# psu_toggle_switch.net
KiCad netlist of a schematic drawn in Altium Designer
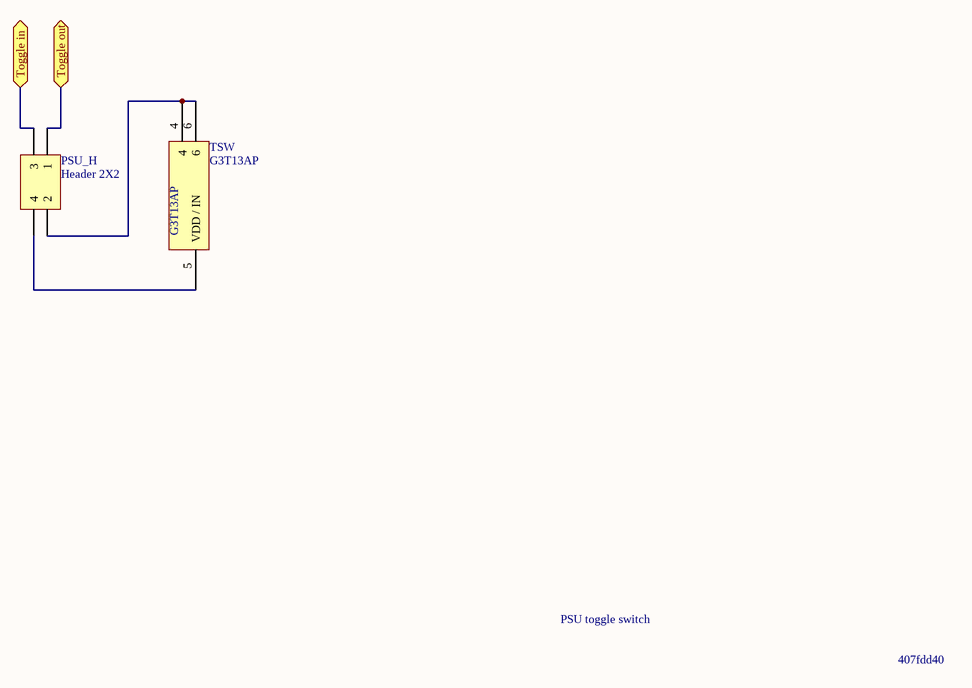
[diagram p0: psu_toggle_switch.SchDoc]

(export (version "E")
  (design (tool "Eeschema 10.0.6"))
  (components
    (comp (ref "PSU_H")
      (value "Header 2X2")
      (footprint "HDR2X2")
      (description "Header, 2-Pin, Dual row")
      (fields (field (name "PUBLISHER") "Altium Limited"))
      (libsource (lib "Miscellaneous Connectors") (part "Header 2X2"))
    )
    (comp (ref "TSW")
      (value "G3T13AP")
      (footprint "G3T13AP")
      (libsource (lib "switch-toggle") (part "G3T13AP"))
    )
  )
  (nets
    (net (code "1") (name "/Toggle in") (class "Default")
      (node (ref "PSU_H") (pin "3") (pinfunction "3_3") (pintype "passive"))
    )
    (net (code "2") (name "/Toggle out") (class "Default")
      (node (ref "PSU_H") (pin "1") (pinfunction "1_1") (pintype "passive"))
    )
    (net (code "3") (name "Net-(PSU_H-Pad2)") (class "Default")
      (node (ref "PSU_H") (pin "2") (pinfunction "2_2") (pintype "passive"))
      (node (ref "TSW") (pin "4") (pinfunction "4_4") (pintype "power_in"))
      (node (ref "TSW") (pin "6") (pinfunction "6_6") (pintype "power_in"))
    )
    (net (code "4") (name "Net-(TSW-VDD_{slash}_IN)") (class "Default")
      (node (ref "PSU_H") (pin "4") (pinfunction "4_4") (pintype "passive"))
      (node (ref "TSW") (pin "5") (pinfunction "VDD_/_IN_5") (pintype "power_in"))
    )
  )
)
